# SCH_WINGLET_SOC.net
KiCad netlist of a schematic drawn in Altium Designer
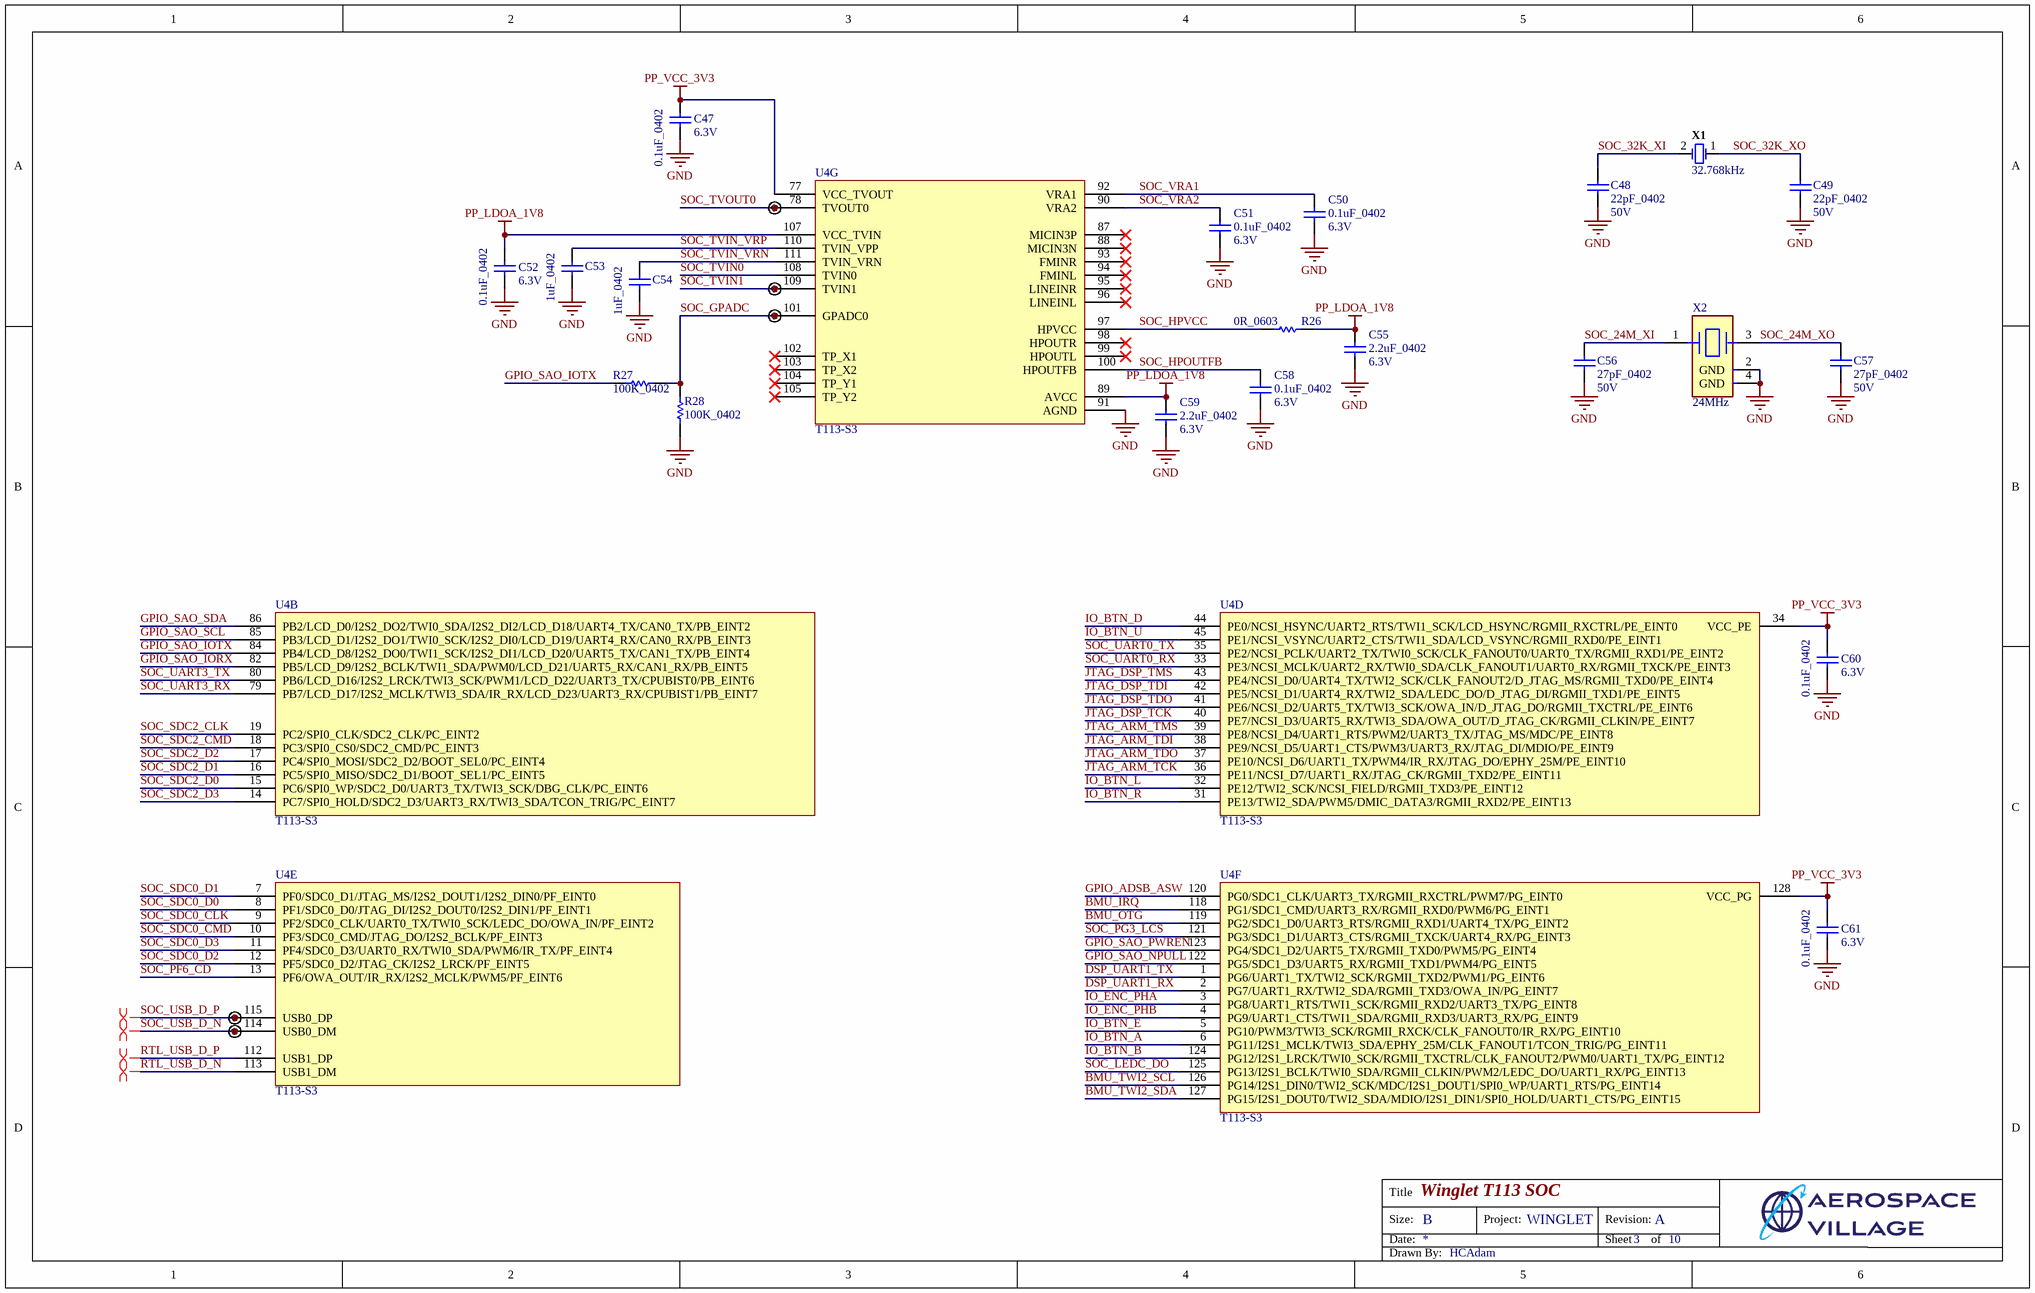
[diagram p0: SCH_WINGLET_SOC.SchDoc]

(export (version "E")
  (design (tool "Eeschema 10.0.6"))
  (components
    (comp (ref "C47")
      (value "0.1uF_0402")
      (footprint "CAPC1005X56X25NL10T15")
      (description "04026D104KAT2A")
      (fields (field (name "MANUFACTURER") "AVX Interconnect / Elco") (field (name "VOLTAGE RATING") "6.3V"))
      (libsource (lib "Altium Content Vault") (part "CAP"))
    )
    (comp (ref "C48")
      (value "22pF_0402")
      (footprint "CAPC1005X56X25LL10T15")
      (description "04025A220JAT2A")
      (fields (field (name "MANUFACTURER") "AVX Interconnect / Elco") (field (name "VOLTAGE RATING") "50V"))
      (libsource (lib "Altium Content Vault") (part "CAP"))
    )
    (comp (ref "C49")
      (value "22pF_0402")
      (footprint "CAPC1005X56X25LL10T15")
      (description "04025A220JAT2A")
      (fields (field (name "MANUFACTURER") "AVX Interconnect / Elco") (field (name "VOLTAGE RATING") "50V"))
      (libsource (lib "Altium Content Vault") (part "CAP"))
    )
    (comp (ref "C50")
      (value "0.1uF_0402")
      (footprint "CAPC1005X56X25NL10T15")
      (description "04026D104KAT2A")
      (fields (field (name "MANUFACTURER") "AVX Interconnect / Elco") (field (name "VOLTAGE RATING") "6.3V"))
      (libsource (lib "Altium Content Vault") (part "CAP"))
    )
    (comp (ref "C51")
      (value "0.1uF_0402")
      (footprint "CAPC1005X56X25NL10T15")
      (description "04026D104KAT2A")
      (fields (field (name "MANUFACTURER") "AVX Interconnect / Elco") (field (name "VOLTAGE RATING") "6.3V"))
      (libsource (lib "Altium Content Vault") (part "CAP"))
    )
    (comp (ref "C52")
      (value "0.1uF_0402")
      (footprint "CAPC1005X56X25NL10T15")
      (description "04026D104KAT2A")
      (fields (field (name "MANUFACTURER") "AVX Interconnect / Elco") (field (name "VOLTAGE RATING") "6.3V"))
      (libsource (lib "Altium Content Vault") (part "CAP"))
    )
    (comp (ref "C53")
      (value "1uF_0402")
      (footprint "CAPC1005X55X25NL5T10")
      (fields (field (name "TOLERANCE") "10%") (field (name "PARTNUMBER") "GRM155R60J105KE19D"))
      (libsource (lib "Altium Content Vault") (part "CAP-NP-2"))
    )
    (comp (ref "C54")
      (value "1uF_0402")
      (footprint "CAPC1005X55X25NL5T10")
      (fields (field (name "TOLERANCE") "10%") (field (name "PARTNUMBER") "GRM155R60J105KE19D"))
      (libsource (lib "Altium Content Vault") (part "CAP-NP-2"))
    )
    (comp (ref "C55")
      (value "2.2uF_0402")
      (footprint "CAPC1005X55X25NL05T10")
      (description "GRM155R60J225ME15D")
      (fields (field (name "MANUFACTURER") "Murata") (field (name "VOLTAGE RATING") "6.3V"))
      (libsource (lib "Altium Content Vault") (part "CAP"))
    )
    (comp (ref "C56")
      (value "27pF_0402")
      (footprint "CAPC1005X55X25ML05T10")
      (description "GRM1555C1H270JA01D")
      (fields (field (name "MANUFACTURER") "Murata") (field (name "VOLTAGE RATING") "50V"))
      (libsource (lib "Altium Content Vault") (part "CAP"))
    )
    (comp (ref "C57")
      (value "27pF_0402")
      (footprint "CAPC1005X55X25ML05T10")
      (description "GRM1555C1H270JA01D")
      (fields (field (name "MANUFACTURER") "Murata") (field (name "VOLTAGE RATING") "50V"))
      (libsource (lib "Altium Content Vault") (part "CAP"))
    )
    (comp (ref "C58")
      (value "0.1uF_0402")
      (footprint "CAPC1005X56X25NL10T15")
      (description "04026D104KAT2A")
      (fields (field (name "MANUFACTURER") "AVX Interconnect / Elco") (field (name "VOLTAGE RATING") "6.3V"))
      (libsource (lib "Altium Content Vault") (part "CAP"))
    )
    (comp (ref "C59")
      (value "2.2uF_0402")
      (footprint "CAPC1005X55X25NL05T10")
      (description "GRM155R60J225ME15D")
      (fields (field (name "MANUFACTURER") "Murata") (field (name "VOLTAGE RATING") "6.3V"))
      (libsource (lib "Altium Content Vault") (part "CAP"))
    )
    (comp (ref "C60")
      (value "0.1uF_0402")
      (footprint "CAPC1005X56X25NL10T15")
      (description "04026D104KAT2A")
      (fields (field (name "MANUFACTURER") "AVX Interconnect / Elco") (field (name "VOLTAGE RATING") "6.3V"))
      (libsource (lib "Altium Content Vault") (part "CAP"))
    )
    (comp (ref "C61")
      (value "0.1uF_0402")
      (footprint "CAPC1005X56X25NL10T15")
      (description "04026D104KAT2A")
      (fields (field (name "MANUFACTURER") "AVX Interconnect / Elco") (field (name "VOLTAGE RATING") "6.3V"))
      (libsource (lib "Altium Content Vault") (part "CAP"))
    )
    (comp (ref "R26")
      (value "0R_0603")
      (footprint "RESC1608X55X25LL10T15")
      (description "RC0603JR-100RL")
      (fields (field (name "MANUFACTURER") "Yageo"))
      (libsource (lib "Altium Content Vault") (part "RES"))
    )
    (comp (ref "R27")
      (value "100K_0402")
      (footprint "RESC1005X40X25NL05T10")
      (description "RC0402FR-07100KL")
      (fields (field (name "MANUFACTURER") "Yageo / Phycomp"))
      (libsource (lib "Altium Content Vault") (part "RES"))
    )
    (comp (ref "R28")
      (value "100K_0402")
      (footprint "RESC1005X40X25NL05T10")
      (description "RC0402FR-07100KL")
      (fields (field (name "MANUFACTURER") "Yageo / Phycomp"))
      (libsource (lib "Altium Content Vault") (part "RES"))
    )
    (comp (ref "TP7")
      (value "TESTPOINT")
      (footprint "TESTPOINT-0.7MM-SINGLE-LAYER")
      (description "TESTPOINT SINGLE LAYER 0.7MM")
      (libsource (lib "DCAV32_WINGLET_SCHLIB") (part "TP_07"))
    )
    (comp (ref "TP8")
      (value "TESTPOINT")
      (footprint "TESTPOINT-0.7MM-SINGLE-LAYER")
      (description "TESTPOINT SINGLE LAYER 0.7MM")
      (libsource (lib "DCAV32_WINGLET_SCHLIB") (part "TP_07"))
    )
    (comp (ref "TP9")
      (value "TESTPOINT")
      (footprint "TESTPOINT-0.7MM-SINGLE-LAYER")
      (description "TESTPOINT SINGLE LAYER 0.7MM")
      (libsource (lib "DCAV32_WINGLET_SCHLIB") (part "TP_07"))
    )
    (comp (ref "TP10")
      (value "TESTPOINT")
      (footprint "TESTPOINT-0.7MM-SINGLE-LAYER")
      (description "TESTPOINT SINGLE LAYER 0.7MM")
      (libsource (lib "DCAV32_WINGLET_SCHLIB") (part "TP_07"))
    )
    (comp (ref "TP11")
      (value "TESTPOINT")
      (footprint "TESTPOINT-0.7MM-SINGLE-LAYER")
      (description "TESTPOINT SINGLE LAYER 0.7MM")
      (libsource (lib "DCAV32_WINGLET_SCHLIB") (part "TP_07"))
    )
    (comp (ref "U4")
      (value "T113-S3")
      (footprint "TSQFP40P1600X1600X160_HS-129N")
      (description "Allwinner Dual-core ARM Cortex-A7 Smart Control and Display SoC")
      (libsource (lib "DCAV32_WINGLET_SCHLIB") (part "T113-S3"))
    )
    (comp (ref "X1")
      (value "32.768kHz")
      (footprint "ABRA-ABS07_A_V")
      (fields (field (name "MANUFACTURER") "Abracon") (field (name "TOLERANCE") "20ppm"))
      (libsource (lib "Altium Content Vault") (part "XTAL-1-2-2"))
    )
    (comp (ref "X2")
      (value "24MHz")
      (footprint "FP-7M-MFG")
      (description "Crystal 24MHz, 30ppm, 12pF, 50Ω\r\n7M-24.000MAAE-T")
      (libsource (lib "Altium Content Vault") (part "41079aabb0e87794b56622915be14ed"))
    )
  )
  (nets
    (net (code "1") (name "/BMU_IRQ") (class "Default")
      (node (ref "U4") (pin "118") (pinfunction "PG1/SDC1_CMD/UART3_RX/RGMII_RXD0/PWM6/PG_EINT1_118") (pintype "passive"))
    )
    (net (code "2") (name "/BMU_OTG") (class "Default")
      (node (ref "U4") (pin "119") (pinfunction "PG2/SDC1_D0/UART3_RTS/RGMII_RXD1/UART4_TX/PG_EINT2_119") (pintype "passive"))
    )
    (net (code "3") (name "/BMU_TWI2_SCL") (class "Default")
      (node (ref "U4") (pin "126") (pinfunction "PG14/I2S1_DIN0/TWI2_SCK/MDC/I2S1_DOUT1/SPI0_WP/UART1_RTS/PG_EINT14_126") (pintype "passive"))
    )
    (net (code "4") (name "/BMU_TWI2_SDA") (class "Default")
      (node (ref "U4") (pin "127") (pinfunction "PG15/I2S1_DOUT0/TWI2_SDA/MDIO/I2S1_DIN1/SPI0_HOLD/UART1_CTS/PG_EINT15_127") (pintype "passive"))
    )
    (net (code "5") (name "/DSP_UART1_RX") (class "Default")
      (node (ref "U4") (pin "2") (pinfunction "PG7/UART1_RX/TWI2_SDA/RGMII_TXD3/OWA_IN/PG_EINT7_2") (pintype "passive"))
    )
    (net (code "6") (name "/DSP_UART1_TX") (class "Default")
      (node (ref "U4") (pin "1") (pinfunction "PG6/UART1_TX/TWI2_SCK/RGMII_TXD2/PWM1/PG_EINT6_1") (pintype "passive"))
    )
    (net (code "7") (name "/GPIO_ADSB_ASW") (class "Default")
      (node (ref "U4") (pin "120") (pinfunction "PG0/SDC1_CLK/UART3_TX/RGMII_RXCTRL/PWM7/PG_EINT0_120") (pintype "passive"))
    )
    (net (code "8") (name "/GPIO_SAO_IORX") (class "Default")
      (node (ref "U4") (pin "82") (pinfunction "PB5/LCD_D9/I2S2_BCLK/TWI1_SDA/PWM0/LCD_D21/UART5_RX/CAN1_RX/PB_EINT5_82") (pintype "passive"))
    )
    (net (code "9") (name "/GPIO_SAO_IOTX") (class "Default")
      (node (ref "R27") (pin "2") (pinfunction "2_2") (pintype "passive"))
      (node (ref "U4") (pin "84") (pinfunction "PB4/LCD_D8/I2S2_DO0/TWI1_SCK/I2S2_DI1/LCD_D20/UART5_TX/CAN1_TX/PB_EINT4_84") (pintype "passive"))
    )
    (net (code "10") (name "/GPIO_SAO_NPULL") (class "Default")
      (node (ref "U4") (pin "122") (pinfunction "PG5/SDC1_D3/UART5_RX/RGMII_TXD1/PWM4/PG_EINT5_122") (pintype "passive"))
    )
    (net (code "11") (name "/GPIO_SAO_PWREN") (class "Default")
      (node (ref "U4") (pin "123") (pinfunction "PG4/SDC1_D2/UART5_TX/RGMII_TXD0/PWM5/PG_EINT4_123") (pintype "passive"))
    )
    (net (code "12") (name "/GPIO_SAO_SCL") (class "Default")
      (node (ref "U4") (pin "85") (pinfunction "PB3/LCD_D1/I2S2_DO1/TWI0_SCK/I2S2_DI0/LCD_D19/UART4_RX/CAN0_RX/PB_EINT3_85") (pintype "passive"))
    )
    (net (code "13") (name "/GPIO_SAO_SDA") (class "Default")
      (node (ref "U4") (pin "86") (pinfunction "PB2/LCD_D0/I2S2_DO2/TWI0_SDA/I2S2_DI2/LCD_D18/UART4_TX/CAN0_TX/PB_EINT2_86") (pintype "passive"))
    )
    (net (code "14") (name "/IO_BTN_A") (class "Default")
      (node (ref "U4") (pin "6") (pinfunction "PG11/I2S1_MCLK/TWI3_SDA/EPHY_25M/CLK_FANOUT1/TCON_TRIG/PG_EINT11_6") (pintype "passive"))
    )
    (net (code "15") (name "/IO_BTN_B") (class "Default")
      (node (ref "U4") (pin "124") (pinfunction "PG12/I2S1_LRCK/TWI0_SCK/RGMII_TXCTRL/CLK_FANOUT2/PWM0/UART1_TX/PG_EINT12_124") (pintype "passive"))
    )
    (net (code "16") (name "/IO_BTN_D") (class "Default")
      (node (ref "U4") (pin "44") (pinfunction "PE0/NCSI_HSYNC/UART2_RTS/TWI1_SCK/LCD_HSYNC/RGMII_RXCTRL/PE_EINT0_44") (pintype "passive"))
    )
    (net (code "17") (name "/IO_BTN_E") (class "Default")
      (node (ref "U4") (pin "5") (pinfunction "PG10/PWM3/TWI3_SCK/RGMII_RXCK/CLK_FANOUT0/IR_RX/PG_EINT10_5") (pintype "passive"))
    )
    (net (code "18") (name "/IO_BTN_L") (class "Default")
      (node (ref "U4") (pin "32") (pinfunction "PE12/TWI2_SCK/NCSI_FIELD/RGMII_TXD3/PE_EINT12_32") (pintype "passive"))
    )
    (net (code "19") (name "/IO_BTN_R") (class "Default")
      (node (ref "U4") (pin "31") (pinfunction "PE13/TWI2_SDA/PWM5/DMIC_DATA3/RGMII_RXD2/PE_EINT13_31") (pintype "passive"))
    )
    (net (code "20") (name "/IO_BTN_U") (class "Default")
      (node (ref "U4") (pin "45") (pinfunction "PE1/NCSI_VSYNC/UART2_CTS/TWI1_SDA/LCD_VSYNC/RGMII_RXD0/PE_EINT1_45") (pintype "passive"))
    )
    (net (code "21") (name "/IO_ENC_PHA") (class "Default")
      (node (ref "U4") (pin "3") (pinfunction "PG8/UART1_RTS/TWI1_SCK/RGMII_RXD2/UART3_TX/PG_EINT8_3") (pintype "passive"))
    )
    (net (code "22") (name "/IO_ENC_PHB") (class "Default")
      (node (ref "U4") (pin "4") (pinfunction "PG9/UART1_CTS/TWI1_SDA/RGMII_RXD3/UART3_RX/PG_EINT9_4") (pintype "passive"))
    )
    (net (code "23") (name "/JTAG_ARM_TCK") (class "Default")
      (node (ref "U4") (pin "36") (pinfunction "PE11/NCSI_D7/UART1_RX/JTAG_CK/RGMII_TXD2/PE_EINT11_36") (pintype "passive"))
    )
    (net (code "24") (name "/JTAG_ARM_TDI") (class "Default")
      (node (ref "U4") (pin "38") (pinfunction "PE9/NCSI_D5/UART1_CTS/PWM3/UART3_RX/JTAG_DI/MDIO/PE_EINT9_38") (pintype "passive"))
    )
    (net (code "25") (name "/JTAG_ARM_TDO") (class "Default")
      (node (ref "U4") (pin "37") (pinfunction "PE10/NCSI_D6/UART1_TX/PWM4/IR_RX/JTAG_DO/EPHY_25M/PE_EINT10_37") (pintype "passive"))
    )
    (net (code "26") (name "/JTAG_ARM_TMS") (class "Default")
      (node (ref "U4") (pin "39") (pinfunction "PE8/NCSI_D4/UART1_RTS/PWM2/UART3_TX/JTAG_MS/MDC/PE_EINT8_39") (pintype "passive"))
    )
    (net (code "27") (name "/JTAG_DSP_TCK") (class "Default")
      (node (ref "U4") (pin "40") (pinfunction "PE7/NCSI_D3/UART5_RX/TWI3_SDA/OWA_OUT/D_JTAG_CK/RGMII_CLKIN/PE_EINT7_40") (pintype "passive"))
    )
    (net (code "28") (name "/JTAG_DSP_TDI") (class "Default")
      (node (ref "U4") (pin "42") (pinfunction "PE5/NCSI_D1/UART4_RX/TWI2_SDA/LEDC_DO/D_JTAG_DI/RGMII_TXD1/PE_EINT5_42") (pintype "passive"))
    )
    (net (code "29") (name "/JTAG_DSP_TDO") (class "Default")
      (node (ref "U4") (pin "41") (pinfunction "PE6/NCSI_D2/UART5_TX/TWI3_SCK/OWA_IN/D_JTAG_DO/RGMII_TXCTRL/PE_EINT6_41") (pintype "passive"))
    )
    (net (code "30") (name "/JTAG_DSP_TMS") (class "Default")
      (node (ref "U4") (pin "43") (pinfunction "PE4/NCSI_D0/UART4_TX/TWI2_SCK/CLK_FANOUT2/D_JTAG_MS/RGMII_TXD0/PE_EINT4_43") (pintype "passive"))
    )
    (net (code "31") (name "/RTL_USB_D_N") (class "Default")
      (node (ref "U4") (pin "113") (pinfunction "USB1_DM_113") (pintype "passive"))
    )
    (net (code "32") (name "/RTL_USB_D_P") (class "Default")
      (node (ref "U4") (pin "112") (pinfunction "USB1_DP_112") (pintype "passive"))
    )
    (net (code "33") (name "/SOC_24M_XI") (class "Default")
      (node (ref "C56") (pin "2") (pinfunction "2_2") (pintype "passive"))
      (node (ref "X2") (pin "1") (pinfunction "1_1") (pintype "passive"))
    )
    (net (code "34") (name "/SOC_24M_XO") (class "Default")
      (node (ref "C57") (pin "2") (pinfunction "2_2") (pintype "passive"))
      (node (ref "X2") (pin "3") (pinfunction "3_3") (pintype "passive"))
    )
    (net (code "35") (name "/SOC_32K_XI") (class "Default")
      (node (ref "C48") (pin "2") (pinfunction "2_2") (pintype "passive"))
      (node (ref "X1") (pin "2") (pinfunction "2_2") (pintype "passive"))
    )
    (net (code "36") (name "/SOC_32K_XO") (class "Default")
      (node (ref "C49") (pin "2") (pinfunction "2_2") (pintype "passive"))
      (node (ref "X1") (pin "1") (pinfunction "1_1") (pintype "passive"))
    )
    (net (code "37") (name "/SOC_GPADC") (class "Default")
      (node (ref "R27") (pin "1") (pinfunction "1_1") (pintype "passive"))
      (node (ref "R28") (pin "2") (pinfunction "2_2") (pintype "passive"))
      (node (ref "TP9") (pin "1") (pinfunction "1_1") (pintype "passive"))
      (node (ref "U4") (pin "101") (pinfunction "GPADC0_101") (pintype "passive"))
    )
    (net (code "38") (name "/SOC_HPOUTFB") (class "Default")
      (node (ref "C58") (pin "2") (pinfunction "2_2") (pintype "passive"))
      (node (ref "U4") (pin "100") (pinfunction "HPOUTFB_100") (pintype "passive"))
    )
    (net (code "39") (name "/SOC_HPVCC") (class "Default")
      (node (ref "R26") (pin "2") (pinfunction "2_2") (pintype "passive"))
      (node (ref "U4") (pin "97") (pinfunction "HPVCC_97") (pintype "passive"))
    )
    (net (code "40") (name "/SOC_LEDC_DO") (class "Default")
      (node (ref "U4") (pin "125") (pinfunction "PG13/I2S1_BCLK/TWI0_SDA/RGMII_CLKIN/PWM2/LEDC_DO/UART1_RX/PG_EINT13_125") (pintype "passive"))
    )
    (net (code "41") (name "/SOC_PF6_CD") (class "Default")
      (node (ref "U4") (pin "13") (pinfunction "PF6/OWA_OUT/IR_RX/I2S2_MCLK/PWM5/PF_EINT6_13") (pintype "passive"))
    )
    (net (code "42") (name "/SOC_PG3_LCS") (class "Default")
      (node (ref "U4") (pin "121") (pinfunction "PG3/SDC1_D1/UART3_CTS/RGMII_TXCK/UART4_RX/PG_EINT3_121") (pintype "passive"))
    )
    (net (code "43") (name "/SOC_SDC0_CLK") (class "Default")
      (node (ref "U4") (pin "9") (pinfunction "PF2/SDC0_CLK/UART0_TX/TWI0_SCK/LEDC_DO/OWA_IN/PF_EINT2_9") (pintype "passive"))
    )
    (net (code "44") (name "/SOC_SDC0_CMD") (class "Default")
      (node (ref "U4") (pin "10") (pinfunction "PF3/SDC0_CMD/JTAG_DO/I2S2_BCLK/PF_EINT3_10") (pintype "passive"))
    )
    (net (code "45") (name "/SOC_SDC0_D0") (class "Default")
      (node (ref "U4") (pin "8") (pinfunction "PF1/SDC0_D0/JTAG_DI/I2S2_DOUT0/I2S2_DIN1/PF_EINT1_8") (pintype "passive"))
    )
    (net (code "46") (name "/SOC_SDC0_D1") (class "Default")
      (node (ref "U4") (pin "7") (pinfunction "PF0/SDC0_D1/JTAG_MS/I2S2_DOUT1/I2S2_DIN0/PF_EINT0_7") (pintype "passive"))
    )
    (net (code "47") (name "/SOC_SDC0_D2") (class "Default")
      (node (ref "U4") (pin "12") (pinfunction "PF5/SDC0_D2/JTAG_CK/I2S2_LRCK/PF_EINT5_12") (pintype "passive"))
    )
    (net (code "48") (name "/SOC_SDC0_D3") (class "Default")
      (node (ref "U4") (pin "11") (pinfunction "PF4/SDC0_D3/UART0_RX/TWI0_SDA/PWM6/IR_TX/PF_EINT4_11") (pintype "passive"))
    )
    (net (code "49") (name "/SOC_SDC2_CLK") (class "Default")
      (node (ref "U4") (pin "19") (pinfunction "PC2/SPI0_CLK/SDC2_CLK/PC_EINT2_19") (pintype "passive"))
    )
    (net (code "50") (name "/SOC_SDC2_CMD") (class "Default")
      (node (ref "U4") (pin "18") (pinfunction "PC3/SPI0_CS0/SDC2_CMD/PC_EINT3_18") (pintype "passive"))
    )
    (net (code "51") (name "/SOC_SDC2_D0") (class "Default")
      (node (ref "U4") (pin "15") (pinfunction "PC6/SPI0_WP/SDC2_D0/UART3_TX/TWI3_SCK/DBG_CLK/PC_EINT6_15") (pintype "passive"))
    )
    (net (code "52") (name "/SOC_SDC2_D1") (class "Default")
      (node (ref "U4") (pin "16") (pinfunction "PC5/SPI0_MISO/SDC2_D1/BOOT_SEL1/PC_EINT5_16") (pintype "passive"))
    )
    (net (code "53") (name "/SOC_SDC2_D2") (class "Default")
      (node (ref "U4") (pin "17") (pinfunction "PC4/SPI0_MOSI/SDC2_D2/BOOT_SEL0/PC_EINT4_17") (pintype "passive"))
    )
    (net (code "54") (name "/SOC_SDC2_D3") (class "Default")
      (node (ref "U4") (pin "14") (pinfunction "PC7/SPI0_HOLD/SDC2_D3/UART3_RX/TWI3_SDA/TCON_TRIG/PC_EINT7_14") (pintype "passive"))
    )
    (net (code "55") (name "/SOC_TVIN0") (class "Default")
      (node (ref "U4") (pin "108") (pinfunction "TVIN0_108") (pintype "passive"))
    )
    (net (code "56") (name "/SOC_TVIN1") (class "Default")
      (node (ref "TP8") (pin "1") (pinfunction "1_1") (pintype "passive"))
      (node (ref "U4") (pin "109") (pinfunction "TVIN1_109") (pintype "passive"))
    )
    (net (code "57") (name "/SOC_TVIN_VRN") (class "Default")
      (node (ref "C54") (pin "2") (pinfunction "2_2") (pintype "passive"))
      (node (ref "U4") (pin "111") (pinfunction "TVIN_VRN_111") (pintype "passive"))
    )
    (net (code "58") (name "/SOC_TVIN_VRP") (class "Default")
      (node (ref "C53") (pin "2") (pinfunction "2_2") (pintype "passive"))
      (node (ref "U4") (pin "110") (pinfunction "TVIN_VPP_110") (pintype "passive"))
    )
    (net (code "59") (name "/SOC_TVOUT0") (class "Default")
      (node (ref "TP7") (pin "1") (pinfunction "1_1") (pintype "passive"))
      (node (ref "U4") (pin "78") (pinfunction "TVOUT0_78") (pintype "passive"))
    )
    (net (code "60") (name "/SOC_UART0_RX") (class "Default")
      (node (ref "U4") (pin "33") (pinfunction "PE3/NCSI_MCLK/UART2_RX/TWI0_SDA/CLK_FANOUT1/UART0_RX/RGMII_TXCK/PE_EINT3_33") (pintype "passive"))
    )
    (net (code "61") (name "/SOC_UART0_TX") (class "Default")
      (node (ref "U4") (pin "35") (pinfunction "PE2/NCSI_PCLK/UART2_TX/TWI0_SCK/CLK_FANOUT0/UART0_TX/RGMII_RXD1/PE_EINT2_35") (pintype "passive"))
    )
    (net (code "62") (name "/SOC_UART3_RX") (class "Default")
      (node (ref "U4") (pin "79") (pinfunction "PB7/LCD_D17/I2S2_MCLK/TWI3_SDA/IR_RX/LCD_D23/UART3_RX/CPUBIST1/PB_EINT7_79") (pintype "passive"))
    )
    (net (code "63") (name "/SOC_UART3_TX") (class "Default")
      (node (ref "U4") (pin "80") (pinfunction "PB6/LCD_D16/I2S2_LRCK/TWI3_SCK/PWM1/LCD_D22/UART3_TX/CPUBIST0/PB_EINT6_80") (pintype "passive"))
    )
    (net (code "64") (name "/SOC_USB_D_N") (class "Default")
      (node (ref "TP11") (pin "1") (pinfunction "1_1") (pintype "passive"))
      (node (ref "U4") (pin "114") (pinfunction "USB0_DM_114") (pintype "passive"))
    )
    (net (code "65") (name "/SOC_USB_D_P") (class "Default")
      (node (ref "TP10") (pin "1") (pinfunction "1_1") (pintype "passive"))
      (node (ref "U4") (pin "115") (pinfunction "USB0_DP_115") (pintype "passive"))
    )
    (net (code "66") (name "/SOC_VRA1") (class "Default")
      (node (ref "C50") (pin "2") (pinfunction "2_2") (pintype "passive"))
      (node (ref "U4") (pin "92") (pinfunction "VRA1_92") (pintype "passive"))
    )
    (net (code "67") (name "/SOC_VRA2") (class "Default")
      (node (ref "C51") (pin "2") (pinfunction "2_2") (pintype "passive"))
      (node (ref "U4") (pin "90") (pinfunction "VRA2_90") (pintype "passive"))
    )
    (net (code "68") (name "GND") (class "Default")
      (node (ref "C47") (pin "1") (pinfunction "1_1") (pintype "passive"))
      (node (ref "C48") (pin "1") (pinfunction "1_1") (pintype "passive"))
      (node (ref "C49") (pin "1") (pinfunction "1_1") (pintype "passive"))
      (node (ref "C50") (pin "1") (pinfunction "1_1") (pintype "passive"))
      (node (ref "C51") (pin "1") (pinfunction "1_1") (pintype "passive"))
      (node (ref "C52") (pin "1") (pinfunction "1_1") (pintype "passive"))
      (node (ref "C53") (pin "1") (pinfunction "1_1") (pintype "passive"))
      (node (ref "C54") (pin "1") (pinfunction "1_1") (pintype "passive"))
      (node (ref "C55") (pin "1") (pinfunction "1_1") (pintype "passive"))
      (node (ref "C56") (pin "1") (pinfunction "1_1") (pintype "passive"))
      (node (ref "C57") (pin "1") (pinfunction "1_1") (pintype "passive"))
      (node (ref "C58") (pin "1") (pinfunction "1_1") (pintype "passive"))
      (node (ref "C59") (pin "1") (pinfunction "1_1") (pintype "passive"))
      (node (ref "C60") (pin "1") (pinfunction "1_1") (pintype "passive"))
      (node (ref "C61") (pin "1") (pinfunction "1_1") (pintype "passive"))
      (node (ref "R28") (pin "1") (pinfunction "1_1") (pintype "passive"))
      (node (ref "U4") (pin "91") (pinfunction "AGND_91") (pintype "passive"))
      (node (ref "X2") (pin "2") (pinfunction "GND_2") (pintype "power_in"))
      (node (ref "X2") (pin "4") (pinfunction "GND_4") (pintype "power_in"))
    )
    (net (code "69") (name "PP_LDOA_1V8") (class "Default")
      (node (ref "C52") (pin "2") (pinfunction "2_2") (pintype "passive"))
      (node (ref "C55") (pin "2") (pinfunction "2_2") (pintype "passive"))
      (node (ref "C59") (pin "2") (pinfunction "2_2") (pintype "passive"))
      (node (ref "R26") (pin "1") (pinfunction "1_1") (pintype "passive"))
      (node (ref "U4") (pin "107") (pinfunction "VCC_TVIN_107") (pintype "passive"))
      (node (ref "U4") (pin "89") (pinfunction "AVCC_89") (pintype "passive"))
    )
    (net (code "70") (name "PP_VCC_3V3") (class "Default")
      (node (ref "C47") (pin "2") (pinfunction "2_2") (pintype "passive"))
      (node (ref "C60") (pin "2") (pinfunction "2_2") (pintype "passive"))
      (node (ref "C61") (pin "2") (pinfunction "2_2") (pintype "passive"))
      (node (ref "U4") (pin "128") (pinfunction "VCC_PG_128") (pintype "passive"))
      (node (ref "U4") (pin "34") (pinfunction "VCC_PE_34") (pintype "passive"))
      (node (ref "U4") (pin "77") (pinfunction "VCC_TVOUT_77") (pintype "passive"))
    )
    (net (code "71") (name "unconnected-(U4G-FMINL-Pad94)") (class "Default")
      (node (ref "U4") (pin "94") (pinfunction "FMINL_94") (pintype "passive+no_connect"))
    )
    (net (code "72") (name "unconnected-(U4G-FMINR-Pad93)") (class "Default")
      (node (ref "U4") (pin "93") (pinfunction "FMINR_93") (pintype "passive+no_connect"))
    )
    (net (code "73") (name "unconnected-(U4G-HPOUTL-Pad99)") (class "Default")
      (node (ref "U4") (pin "99") (pinfunction "HPOUTL_99") (pintype "passive+no_connect"))
    )
    (net (code "74") (name "unconnected-(U4G-HPOUTR-Pad98)") (class "Default")
      (node (ref "U4") (pin "98") (pinfunction "HPOUTR_98") (pintype "passive+no_connect"))
    )
    (net (code "75") (name "unconnected-(U4G-LINEINL-Pad96)") (class "Default")
      (node (ref "U4") (pin "96") (pinfunction "LINEINL_96") (pintype "passive+no_connect"))
    )
    (net (code "76") (name "unconnected-(U4G-LINEINR-Pad95)") (class "Default")
      (node (ref "U4") (pin "95") (pinfunction "LINEINR_95") (pintype "passive+no_connect"))
    )
    (net (code "77") (name "unconnected-(U4G-MICIN3N-Pad88)") (class "Default")
      (node (ref "U4") (pin "88") (pinfunction "MICIN3N_88") (pintype "passive+no_connect"))
    )
    (net (code "78") (name "unconnected-(U4G-MICIN3P-Pad87)") (class "Default")
      (node (ref "U4") (pin "87") (pinfunction "MICIN3P_87") (pintype "passive+no_connect"))
    )
    (net (code "79") (name "unconnected-(U4G-TP_X1-Pad102)") (class "Default")
      (node (ref "U4") (pin "102") (pinfunction "TP_X1_102") (pintype "passive+no_connect"))
    )
    (net (code "80") (name "unconnected-(U4G-TP_X2-Pad103)") (class "Default")
      (node (ref "U4") (pin "103") (pinfunction "TP_X2_103") (pintype "passive+no_connect"))
    )
    (net (code "81") (name "unconnected-(U4G-TP_Y1-Pad104)") (class "Default")
      (node (ref "U4") (pin "104") (pinfunction "TP_Y1_104") (pintype "passive+no_connect"))
    )
    (net (code "82") (name "unconnected-(U4G-TP_Y2-Pad105)") (class "Default")
      (node (ref "U4") (pin "105") (pinfunction "TP_Y2_105") (pintype "passive+no_connect"))
    )
  )
)
